# ADS1299DRV.net
KiCad netlist of a schematic drawn in Altium Designer
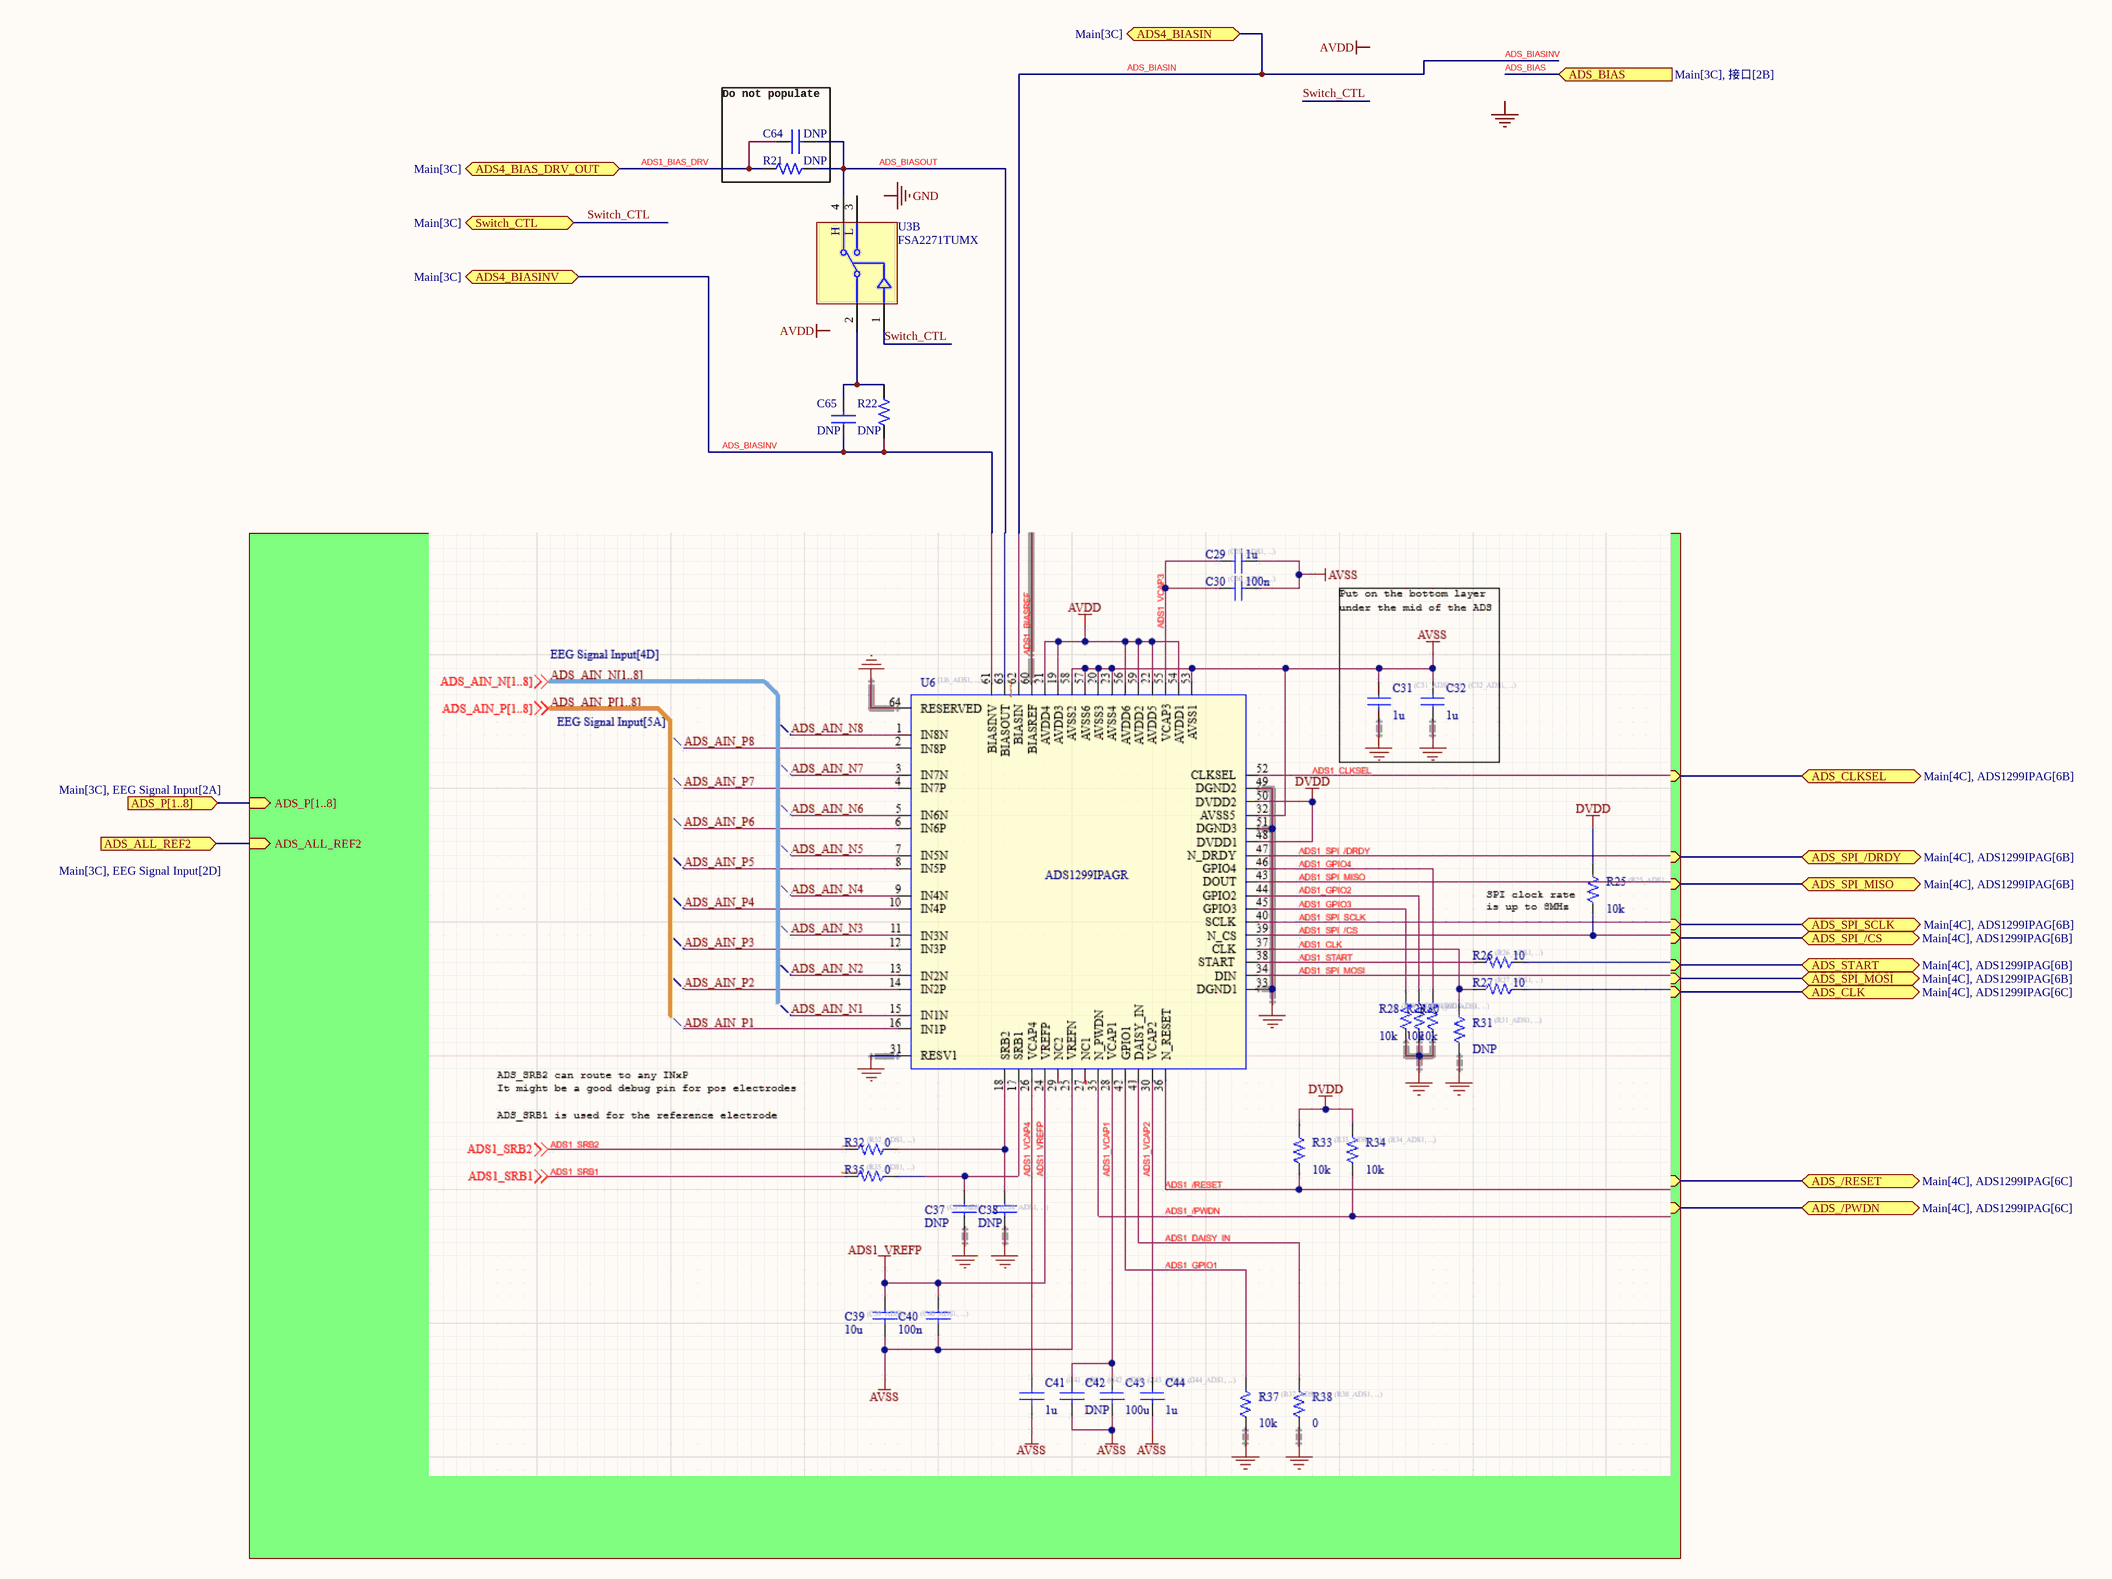
[diagram p0: ADS1299DRV.SchDoc]

(export (version "E")
  (design (tool "Eeschema 10.0.6"))
  (components
    (comp (ref "C64") (value "DNP") (footprint "0402_C") (libsource (lib "*") (part "CAP0402")))
    (comp (ref "C65") (value "DNP") (footprint "0402_C") (libsource (lib "*") (part "CAP0402")))
    (comp (ref "R21") (value "DNP") (footprint "0402_R") (libsource (lib "*") (part "RES")))
    (comp (ref "R22") (value "DNP") (footprint "0402_R") (libsource (lib "*") (part "RES")))
    (comp (ref "U3")
      (value "FSA2271TUMX")
      (footprint "UFQFN-10(1.4x1.8)")
      (libsource (lib "RFID") (part "FSA2271TUMX"))
    )
  )
  (nets
    (net (code "9") (name "/ADS1_BIAS_DRV") (class "Default")
      (node (ref "C64") (pin "1") (pinfunction "1_1") (pintype "passive"))
      (node (ref "R21") (pin "2") (pinfunction "2_2") (pintype "passive"))
    )
    (net (code "12") (name "/ADS_BIASIN") (class "Default")
      (node (ref "C65") (pin "1") (pinfunction "1_1") (pintype "passive"))
      (node (ref "R22") (pin "2") (pinfunction "2_2") (pintype "passive"))
    )
    (net (code "13") (name "/ADS_BIASOUT") (class "Default")
      (node (ref "C64") (pin "2") (pinfunction "2_2") (pintype "passive"))
      (node (ref "R21") (pin "1") (pinfunction "1_1") (pintype "passive"))
      (node (ref "U3") (pin "4") (pinfunction "2B1_4") (pintype "passive"))
    )
    (net (code "25") (name "/Switch_CTL") (class "Default")
      (node (ref "U3") (pin "1") (pinfunction "S2_1") (pintype "passive"))
    )
    (net (code "28") (name "Net-(U3B-2A)") (class "Default")
      (node (ref "C65") (pin "2") (pinfunction "2_2") (pintype "passive"))
      (node (ref "R22") (pin "1") (pinfunction "1_1") (pintype "passive"))
      (node (ref "U3") (pin "2") (pinfunction "2A_2") (pintype "passive"))
    )
    (net (code "29") (name "unconnected-(U3B-2B0-Pad3)") (class "Default")
      (node (ref "U3") (pin "3") (pinfunction "2B0_3") (pintype "passive"))
    )
  )
)
